# DorothiController.net
KiCad netlist of a schematic drawn in EAGLE
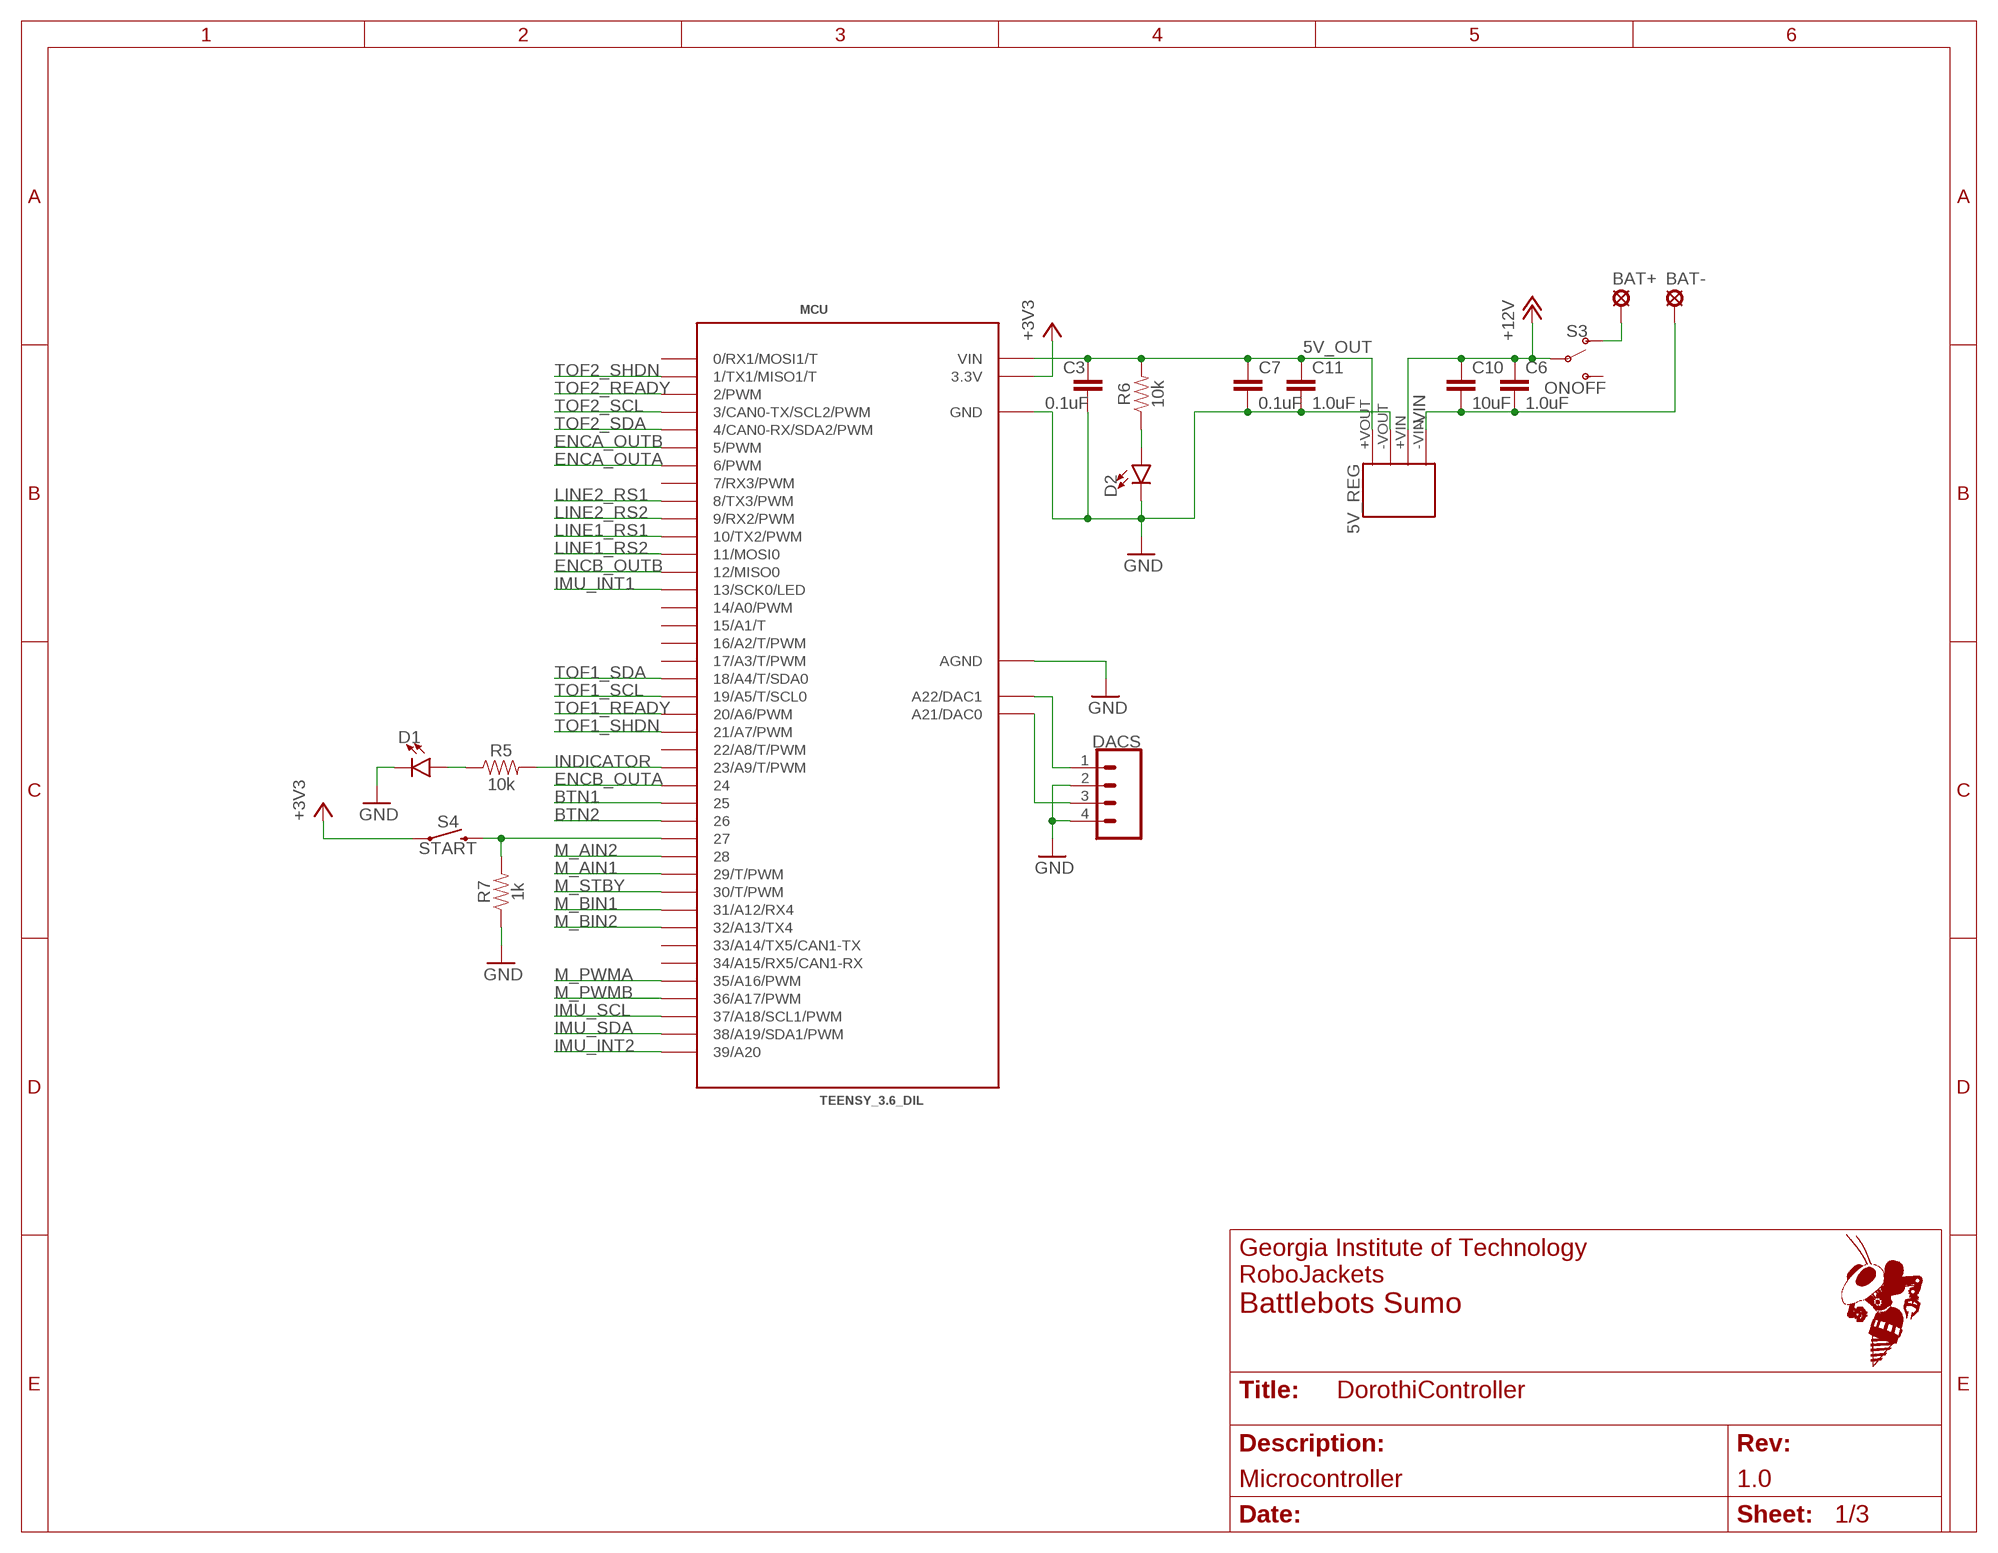
[diagram p0: schematic, sheet 1]
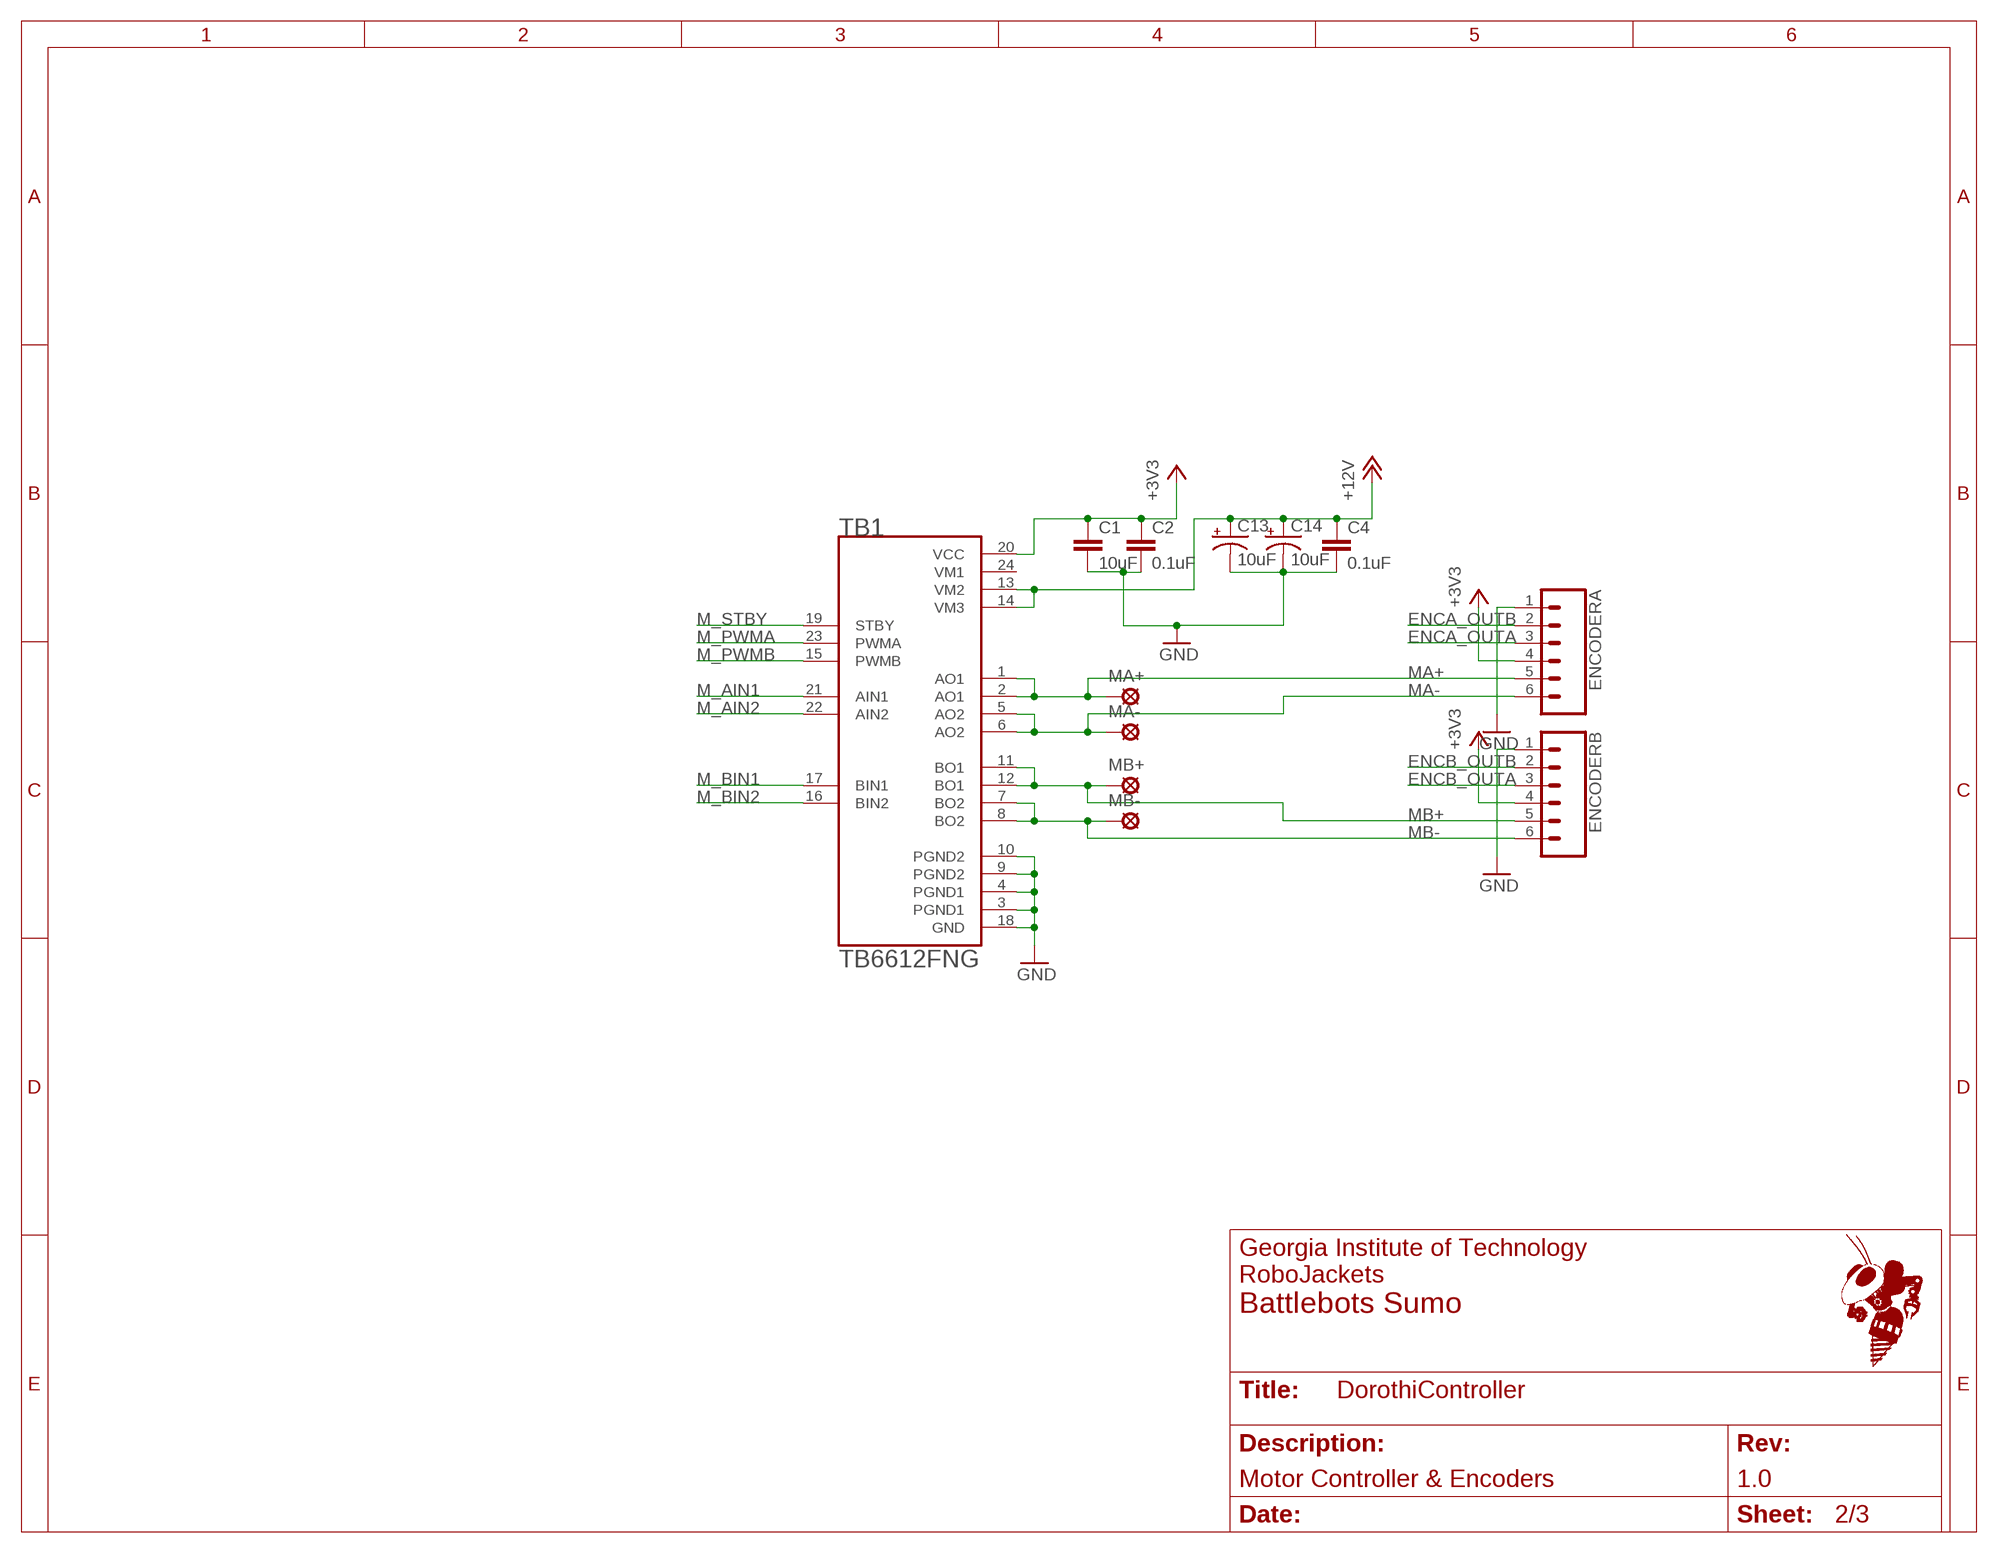
[diagram p1: schematic, sheet 2]
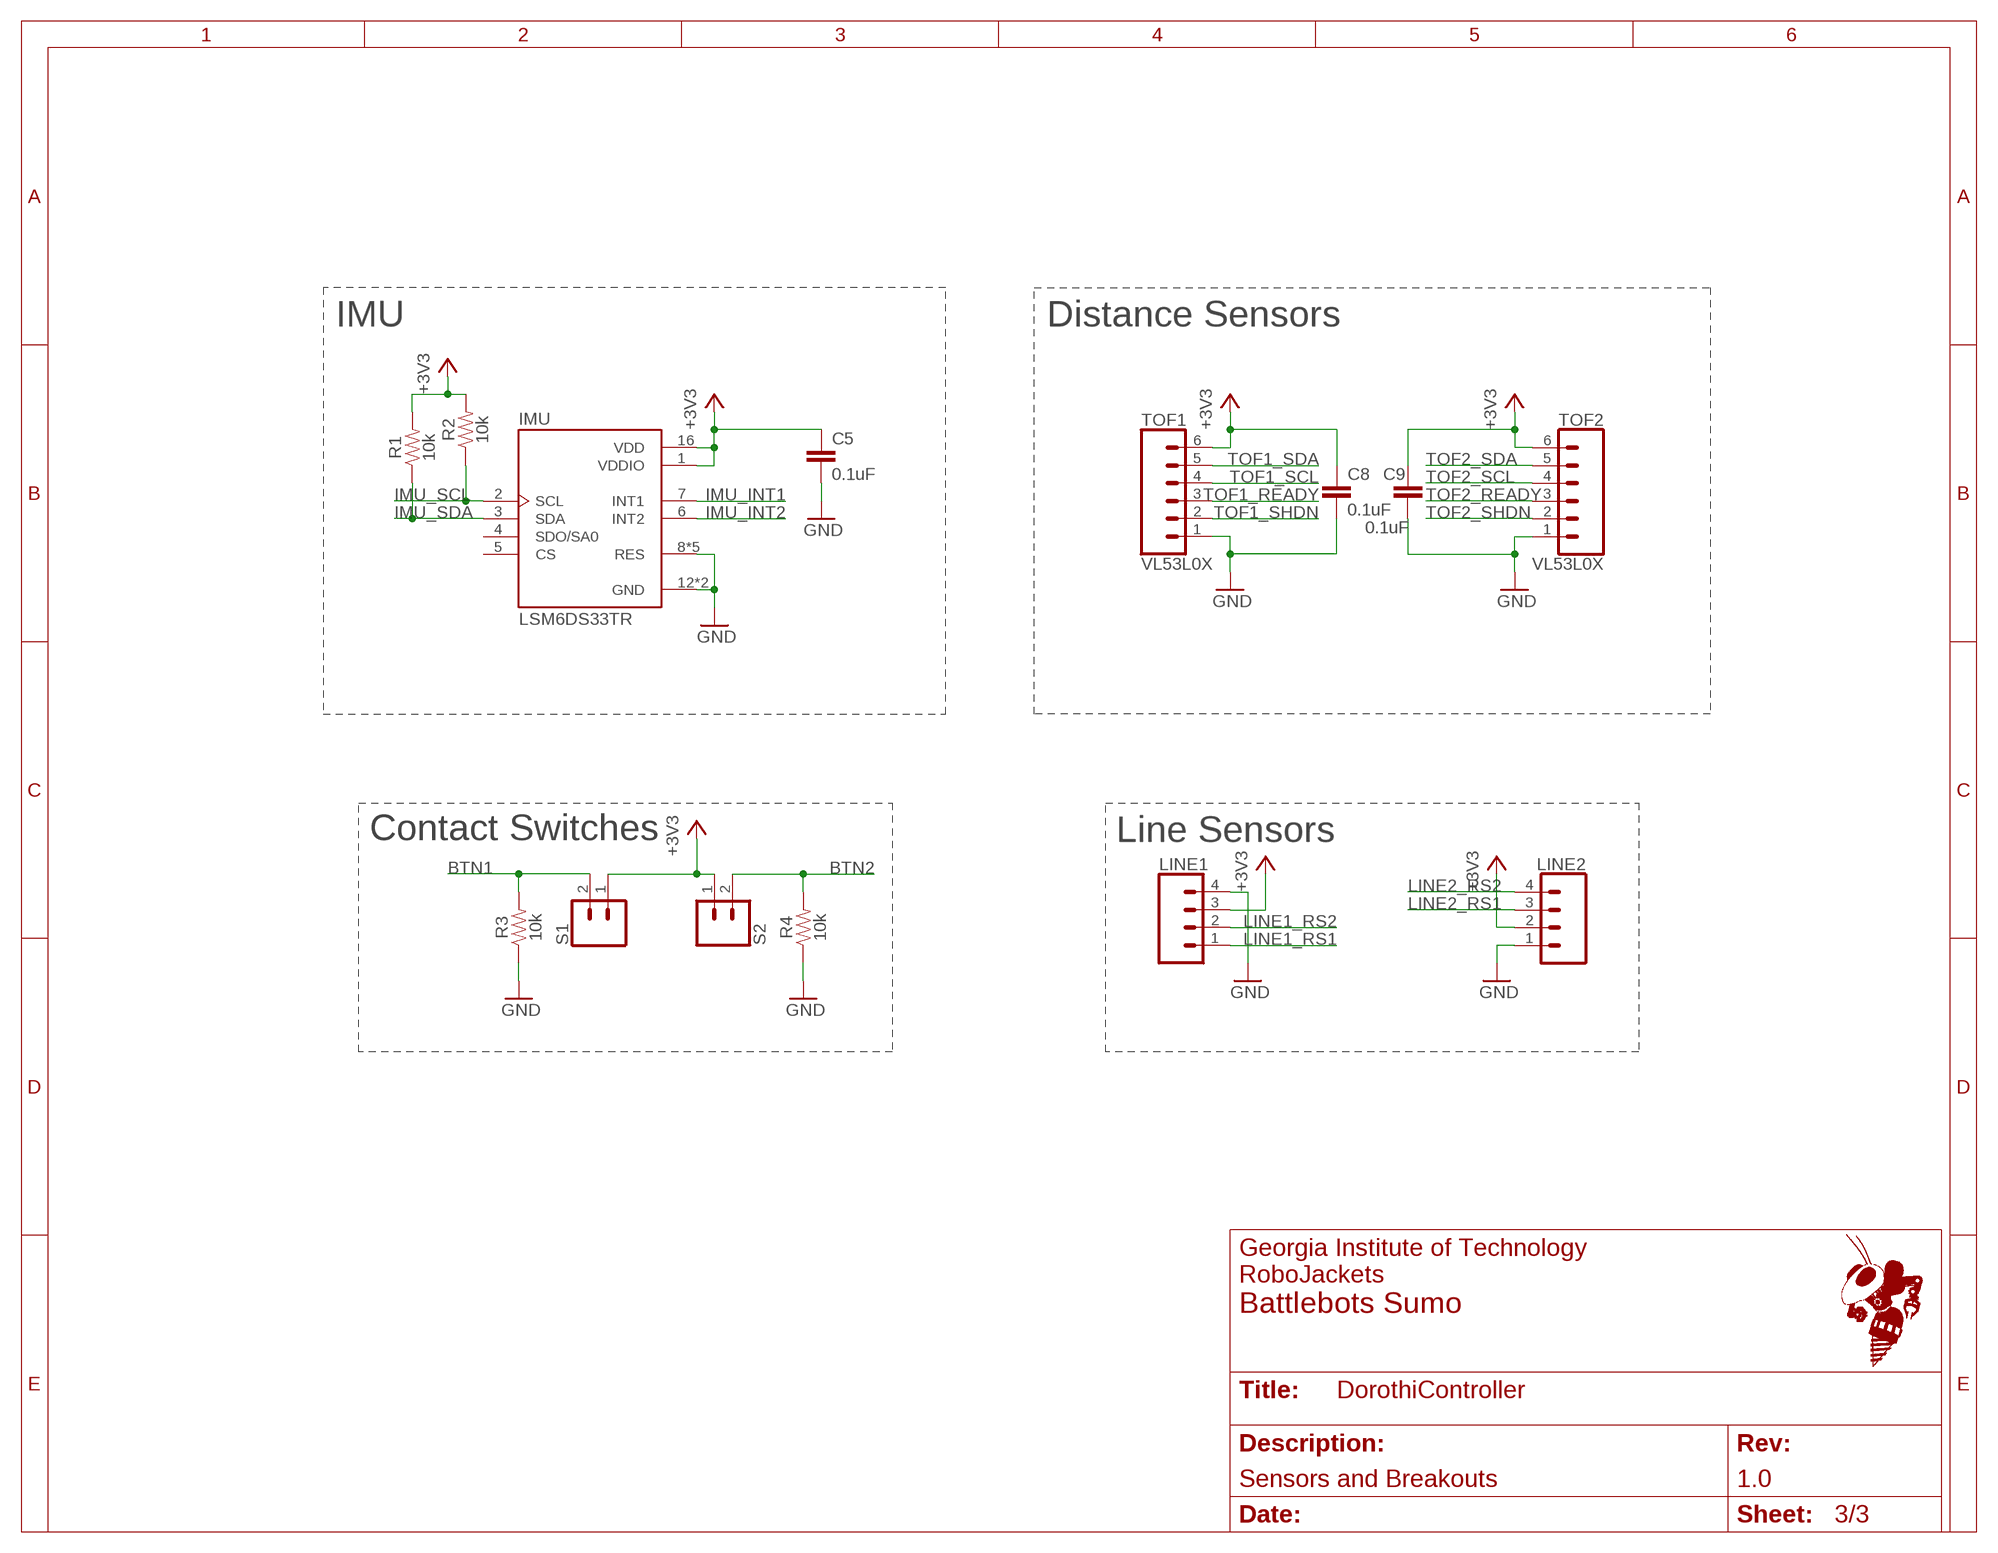
[diagram p2: schematic, sheet 3]

(export (version "E")
  (design (tool "Eeschema 10.0.6"))
  (components
    (comp (ref "C1")
      (value "10uF")
      (footprint "eagle-import:0603")
      (libsource (lib "eagle-import") (part "10UF-0603-6.3V-20%"))
    )
    (comp (ref "C2")
      (value "0.1uF")
      (footprint "eagle-import:0603")
      (libsource (lib "eagle-import") (part "0.1UF-0603-25V-5%"))
    )
    (comp (ref "C4")
      (value "0.1uF")
      (footprint "eagle-import:0603")
      (libsource (lib "eagle-import") (part "0.1UF-0603-25V-5%"))
    )
    (comp (ref "C13")
      (value "10uF")
      (footprint "eagle-import:0603-POLAR")
      (libsource (lib "eagle-import") (part "10UF-POLAR-0603-6.3V-20%(TANT)"))
    )
    (comp (ref "C14")
      (value "10uF")
      (footprint "eagle-import:0603-POLAR")
      (libsource (lib "eagle-import") (part "10UF-POLAR-0603-6.3V-20%(TANT)"))
    )
    (comp (ref "ENCODERA")
      (value "CONN_06SILK_FEMALE_PTH")
      (footprint "eagle-import:1X06")
      (libsource (lib "eagle-import") (part "CONN_06SILK_FEMALE_PTH"))
    )
    (comp (ref "ENCODERB")
      (value "CONN_06SILK_FEMALE_PTH")
      (footprint "eagle-import:1X06")
      (libsource (lib "eagle-import") (part "CONN_06SILK_FEMALE_PTH"))
    )
    (comp (ref "MA+")
      (value "24_SOLPAD")
      (footprint "eagle-import:WIRE_SOLPAD")
      (libsource (lib "eagle-import") (part "24_SOLPAD"))
    )
    (comp (ref "MA-")
      (value "24_SOLPAD")
      (footprint "eagle-import:WIRE_SOLPAD")
      (libsource (lib "eagle-import") (part "24_SOLPAD"))
    )
    (comp (ref "MB+")
      (value "24_SOLPAD")
      (footprint "eagle-import:WIRE_SOLPAD")
      (libsource (lib "eagle-import") (part "24_SOLPAD"))
    )
    (comp (ref "MB-")
      (value "24_SOLPAD")
      (footprint "eagle-import:WIRE_SOLPAD")
      (libsource (lib "eagle-import") (part "24_SOLPAD"))
    )
    (comp (ref "TB1")
      (value "TB6612FNG")
      (footprint "eagle-import:SOP65P760X160-24N")
      (fields (field (name "MF") "Toshiba") (field (name "MP") "TB6612FNG_O,C,8,EL"))
      (libsource (lib "eagle-import") (part "TB6612FNG(O,C,8,EL"))
    )
    (comp (ref "C5")
      (value "0.1uF")
      (footprint "eagle-import:0603")
      (libsource (lib "eagle-import") (part "0.1UF-0603-25V-5%"))
    )
    (comp (ref "C8")
      (value "0.1uF")
      (footprint "eagle-import:0603")
      (libsource (lib "eagle-import") (part "0.1UF-0603-25V-5%"))
    )
    (comp (ref "C9")
      (value "0.1uF")
      (footprint "eagle-import:0603")
      (libsource (lib "eagle-import") (part "0.1UF-0603-25V-5%"))
    )
    (comp (ref "IMU")
      (value "LSM6DS33TR")
      (footprint "eagle-import:PQFN50P300X300X86-16N")
      (fields (field (name "MF") "STMicroelectronics"))
      (libsource (lib "eagle-import") (part "LSM6DS33TR"))
    )
    (comp (ref "LINE1")
      (value "CONN_04")
      (footprint "eagle-import:1X04")
      (libsource (lib "eagle-import") (part "CONN_04"))
    )
    (comp (ref "LINE2")
      (value "CONN_04")
      (footprint "eagle-import:1X04")
      (libsource (lib "eagle-import") (part "CONN_04"))
    )
    (comp (ref "R1")
      (value "10k")
      (footprint "eagle-import:0603")
      (libsource (lib "eagle-import") (part "10KOHM-0603-1/10W-1%"))
    )
    (comp (ref "R2")
      (value "10k")
      (footprint "eagle-import:0603")
      (libsource (lib "eagle-import") (part "10KOHM-0603-1/10W-1%"))
    )
    (comp (ref "R3")
      (value "10k")
      (footprint "eagle-import:0603")
      (libsource (lib "eagle-import") (part "10KOHM-0603-1/10W-1%"))
    )
    (comp (ref "R4")
      (value "10k")
      (footprint "eagle-import:0603")
      (libsource (lib "eagle-import") (part "10KOHM-0603-1/10W-1%"))
    )
    (comp (ref "S1")
      (value "CONN_02")
      (footprint "eagle-import:1X02")
      (libsource (lib "eagle-import") (part "CONN_02"))
    )
    (comp (ref "S2")
      (value "CONN_02")
      (footprint "eagle-import:1X02")
      (libsource (lib "eagle-import") (part "CONN_02"))
    )
    (comp (ref "TOF1")
      (value "VL53L0X")
      (footprint "eagle-import:1X06")
      (libsource (lib "eagle-import") (part "CONN_06SILK_FEMALE_PTH"))
    )
    (comp (ref "TOF2")
      (value "VL53L0X")
      (footprint "eagle-import:1X06")
      (libsource (lib "eagle-import") (part "CONN_06SILK_FEMALE_PTH"))
    )
    (comp (ref "5V_REG")
      (value "CRE1S1205SC")
      (footprint "eagle-import:CRE1S1205SC")
      (libsource (lib "eagle-import") (part "CRE1S1205SC"))
    )
    (comp (ref "BAT+")
      (value "24_SOLPAD")
      (footprint "eagle-import:WIRE_SOLPAD")
      (libsource (lib "eagle-import") (part "24_SOLPAD"))
    )
    (comp (ref "BAT-")
      (value "24_SOLPAD")
      (footprint "eagle-import:WIRE_SOLPAD")
      (libsource (lib "eagle-import") (part "24_SOLPAD"))
    )
    (comp (ref "C3")
      (value "0.1uF")
      (footprint "eagle-import:0603")
      (libsource (lib "eagle-import") (part "SparkFun-Capacitors_510_0.1UF-0603-25V-(+80/-20%)"))
    )
    (comp (ref "C6")
      (value "1.0uF")
      (footprint "eagle-import:0603")
      (libsource (lib "eagle-import") (part "1.0UF-0603-16V-10%"))
    )
    (comp (ref "C7")
      (value "0.1uF")
      (footprint "eagle-import:0603")
      (libsource (lib "eagle-import") (part "SparkFun-Capacitors_510_0.1UF-0603-25V-(+80/-20%)"))
    )
    (comp (ref "C10")
      (value "10uF")
      (footprint "eagle-import:0603")
      (libsource (lib "eagle-import") (part "10UF-0603-6.3V-20%"))
    )
    (comp (ref "C11")
      (value "1.0uF")
      (footprint "eagle-import:0603")
      (libsource (lib "eagle-import") (part "1.0UF-0603-16V-10%"))
    )
    (comp (ref "D1")
      (value "LED0603")
      (footprint "eagle-import:LED-0603")
      (libsource (lib "eagle-import") (part "LED0603"))
    )
    (comp (ref "D2")
      (value "LED0603")
      (footprint "eagle-import:LED-0603")
      (libsource (lib "eagle-import") (part "LED0603"))
    )
    (comp (ref "DACS")
      (value "CONN_04")
      (footprint "eagle-import:1X04")
      (libsource (lib "eagle-import") (part "CONN_04"))
    )
    (comp (ref "MCU")
      (value "TEENSY_3.6_DIL")
      (footprint "eagle-import:TEENSY_3.6_DIL")
      (libsource (lib "eagle-import") (part "TEENSY_3.6_DIL"))
    )
    (comp (ref "R5")
      (value "10k")
      (footprint "eagle-import:0603")
      (libsource (lib "eagle-import") (part "10KOHM-0603-1/10W-1%"))
    )
    (comp (ref "R6")
      (value "10k")
      (footprint "eagle-import:0603")
      (libsource (lib "eagle-import") (part "10KOHM-0603-1/10W-1%"))
    )
    (comp (ref "R7")
      (value "1k")
      (footprint "eagle-import:0603")
      (libsource (lib "eagle-import") (part "1KOHM-0603-1/10W-1%"))
    )
    (comp (ref "S3")
      (value "ONOFF")
      (footprint "eagle-import:SWITCH_SPDT_PTH_11.6X4.0MM")
      (libsource (lib "eagle-import") (part "SWITCH-SPDT-PTH-11.6X4.0MM"))
    )
    (comp (ref "S4")
      (value "START")
      (footprint "eagle-import:TACTILE_SWITCH_SMD_6.0X3.5MM")
      (libsource (lib "eagle-import") (part "MOMENTARY-SWITCH-SPST-SMD-6.0X3.5MM"))
    )
  )
  (nets
    (net (code "1") (name "+3V3") (class "Default")
      (node (ref "C1") (pin "1") (pinfunction "1_1") (pintype "passive"))
      (node (ref "C2") (pin "1") (pinfunction "1_1") (pintype "passive"))
      (node (ref "C5") (pin "1") (pinfunction "1_1") (pintype "passive"))
      (node (ref "C8") (pin "1") (pinfunction "1_1") (pintype "passive"))
      (node (ref "C9") (pin "1") (pinfunction "1_1") (pintype "passive"))
      (node (ref "ENCODERA") (pin "4") (pinfunction "4_4") (pintype "passive"))
      (node (ref "ENCODERB") (pin "4") (pinfunction "4_4") (pintype "passive"))
      (node (ref "IMU") (pin "1") (pinfunction "VDDIO_1") (pintype "power_in"))
      (node (ref "IMU") (pin "16") (pinfunction "VDD_16") (pintype "power_in"))
      (node (ref "LINE1") (pin "3") (pinfunction "3_3") (pintype "passive"))
      (node (ref "LINE2") (pin "2") (pinfunction "2_2") (pintype "passive"))
      (node (ref "MCU") (pin "3.3V") (pinfunction "3.3V_3.3V") (pintype "power_in"))
      (node (ref "MCU") (pin "3.3V3") (pinfunction "3.3V_3.3V3") (pintype "power_in"))
      (node (ref "R1") (pin "2") (pinfunction "2_2") (pintype "passive"))
      (node (ref "R2") (pin "2") (pinfunction "2_2") (pintype "passive"))
      (node (ref "S1") (pin "1") (pinfunction "1_1") (pintype "passive"))
      (node (ref "S2") (pin "1") (pinfunction "1_1") (pintype "passive"))
      (node (ref "S4") (pin "1") (pinfunction "1_1") (pintype "passive"))
      (node (ref "TB1") (pin "20") (pinfunction "VCC_20") (pintype "power_in"))
      (node (ref "TOF1") (pin "6") (pinfunction "6_6") (pintype "passive"))
      (node (ref "TOF2") (pin "6") (pinfunction "6_6") (pintype "passive"))
    )
    (net (code "2") (name "+12V") (class "Default")
      (node (ref "5V_REG") (pin "+VIN") (pinfunction "+VIN_+VIN") (pintype "bidirectional"))
      (node (ref "C10") (pin "1") (pinfunction "1_1") (pintype "passive"))
      (node (ref "C13") (pin "+") (pinfunction "+_+") (pintype "passive"))
      (node (ref "C14") (pin "+") (pinfunction "+_+") (pintype "passive"))
      (node (ref "C4") (pin "1") (pinfunction "1_1") (pintype "passive"))
      (node (ref "C6") (pin "1") (pinfunction "1_1") (pintype "passive"))
      (node (ref "S3") (pin "2") (pinfunction "P_2") (pintype "passive"))
      (node (ref "TB1") (pin "13") (pinfunction "VM2_13") (pintype "power_in"))
      (node (ref "TB1") (pin "14") (pinfunction "VM3_14") (pintype "power_in"))
    )
    (net (code "3") (name "-VIN") (class "Default")
      (node (ref "5V_REG") (pin "-VIN") (pinfunction "-VIN_-VIN") (pintype "bidirectional"))
      (node (ref "BAT-") (pin "P$1") (pinfunction "MP_P$1") (pintype "passive"))
      (node (ref "C10") (pin "2") (pinfunction "2_2") (pintype "passive"))
      (node (ref "C6") (pin "2") (pinfunction "2_2") (pintype "passive"))
    )
    (net (code "4") (name "5V_OUT") (class "Default")
      (node (ref "5V_REG") (pin "+VOUT") (pinfunction "+VOUT_+VOUT") (pintype "bidirectional"))
      (node (ref "C11") (pin "1") (pinfunction "1_1") (pintype "passive"))
      (node (ref "C3") (pin "1") (pinfunction "1_1") (pintype "passive"))
      (node (ref "C7") (pin "1") (pinfunction "1_1") (pintype "passive"))
      (node (ref "MCU") (pin "VIN") (pinfunction "VIN_VIN") (pintype "power_in"))
      (node (ref "R6") (pin "2") (pinfunction "2_2") (pintype "passive"))
    )
    (net (code "5") (name "BTN1") (class "Default")
      (node (ref "MCU") (pin "25") (pinfunction "25_25") (pintype "bidirectional"))
      (node (ref "R3") (pin "2") (pinfunction "2_2") (pintype "passive"))
      (node (ref "S1") (pin "2") (pinfunction "2_2") (pintype "passive"))
    )
    (net (code "6") (name "BTN2") (class "Default")
      (node (ref "MCU") (pin "26") (pinfunction "26_26") (pintype "bidirectional"))
      (node (ref "R4") (pin "2") (pinfunction "2_2") (pintype "passive"))
      (node (ref "S2") (pin "2") (pinfunction "2_2") (pintype "passive"))
    )
    (net (code "7") (name "ENCA_OUTA") (class "Default")
      (node (ref "ENCODERA") (pin "3") (pinfunction "3_3") (pintype "passive"))
      (node (ref "MCU") (pin "6") (pinfunction "6/PWM_6") (pintype "bidirectional"))
    )
    (net (code "8") (name "ENCA_OUTB") (class "Default")
      (node (ref "ENCODERA") (pin "2") (pinfunction "2_2") (pintype "passive"))
      (node (ref "MCU") (pin "5") (pinfunction "5/PWM_5") (pintype "bidirectional"))
    )
    (net (code "9") (name "ENCB_OUTA") (class "Default")
      (node (ref "ENCODERB") (pin "3") (pinfunction "3_3") (pintype "passive"))
      (node (ref "MCU") (pin "24") (pinfunction "24_24") (pintype "bidirectional"))
    )
    (net (code "10") (name "ENCB_OUTB") (class "Default")
      (node (ref "ENCODERB") (pin "2") (pinfunction "2_2") (pintype "passive"))
      (node (ref "MCU") (pin "12") (pinfunction "12/MISO0_12") (pintype "bidirectional"))
    )
    (net (code "11") (name "GND") (class "Default")
      (node (ref "5V_REG") (pin "-VOUT") (pinfunction "-VOUT_-VOUT") (pintype "bidirectional"))
      (node (ref "C1") (pin "2") (pinfunction "2_2") (pintype "passive"))
      (node (ref "C11") (pin "2") (pinfunction "2_2") (pintype "passive"))
      (node (ref "C13") (pin "-") (pinfunction "-_-") (pintype "passive"))
      (node (ref "C14") (pin "-") (pinfunction "-_-") (pintype "passive"))
      (node (ref "C2") (pin "2") (pinfunction "2_2") (pintype "passive"))
      (node (ref "C3") (pin "2") (pinfunction "2_2") (pintype "passive"))
      (node (ref "C4") (pin "2") (pinfunction "2_2") (pintype "passive"))
      (node (ref "C5") (pin "2") (pinfunction "2_2") (pintype "passive"))
      (node (ref "C7") (pin "2") (pinfunction "2_2") (pintype "passive"))
      (node (ref "C8") (pin "2") (pinfunction "2_2") (pintype "passive"))
      (node (ref "C9") (pin "2") (pinfunction "2_2") (pintype "passive"))
      (node (ref "D1") (pin "C") (pinfunction "C_C") (pintype "passive"))
      (node (ref "D2") (pin "C") (pinfunction "C_C") (pintype "passive"))
      (node (ref "DACS") (pin "2") (pinfunction "2_2") (pintype "passive"))
      (node (ref "DACS") (pin "4") (pinfunction "4_4") (pintype "passive"))
      (node (ref "ENCODERA") (pin "1") (pinfunction "1_1") (pintype "passive"))
      (node (ref "ENCODERB") (pin "1") (pinfunction "1_1") (pintype "passive"))
      (node (ref "IMU") (pin "10") (pinfunction "RES_10") (pintype "passive"))
      (node (ref "IMU") (pin "11") (pinfunction "RES_11") (pintype "passive"))
      (node (ref "IMU") (pin "12") (pinfunction "GND_12") (pintype "power_in"))
      (node (ref "IMU") (pin "13") (pinfunction "GND_13") (pintype "power_in"))
      (node (ref "IMU") (pin "15") (pinfunction "RES_15") (pintype "passive"))
      (node (ref "IMU") (pin "8") (pinfunction "RES_8") (pintype "passive"))
      (node (ref "IMU") (pin "9") (pinfunction "RES_9") (pintype "passive"))
      (node (ref "LINE1") (pin "4") (pinfunction "4_4") (pintype "passive"))
      (node (ref "LINE2") (pin "1") (pinfunction "1_1") (pintype "passive"))
      (node (ref "MCU") (pin "AGND") (pinfunction "AGND_AGND") (pintype "power_in"))
      (node (ref "MCU") (pin "GND") (pinfunction "GND_GND") (pintype "power_in"))
      (node (ref "MCU") (pin "GND1") (pinfunction "GND_GND1") (pintype "power_in"))
      (node (ref "R3") (pin "1") (pinfunction "1_1") (pintype "passive"))
      (node (ref "R4") (pin "1") (pinfunction "1_1") (pintype "passive"))
      (node (ref "R7") (pin "1") (pinfunction "1_1") (pintype "passive"))
      (node (ref "TB1") (pin "10") (pinfunction "PGND2_10") (pintype "passive"))
      (node (ref "TB1") (pin "18") (pinfunction "GND_18") (pintype "passive"))
      (node (ref "TB1") (pin "3") (pinfunction "PGND1_3") (pintype "passive"))
      (node (ref "TB1") (pin "4") (pinfunction "PGND1_4") (pintype "passive"))
      (node (ref "TB1") (pin "9") (pinfunction "PGND2_9") (pintype "passive"))
      (node (ref "TOF1") (pin "1") (pinfunction "1_1") (pintype "passive"))
      (node (ref "TOF2") (pin "1") (pinfunction "1_1") (pintype "passive"))
    )
    (net (code "12") (name "IMU_INT1") (class "Default")
      (node (ref "IMU") (pin "7") (pinfunction "INT1_7") (pintype "output"))
      (node (ref "MCU") (pin "13") (pinfunction "13/SCK0/LED_13") (pintype "bidirectional"))
    )
    (net (code "13") (name "IMU_INT2") (class "Default")
      (node (ref "IMU") (pin "6") (pinfunction "INT2_6") (pintype "output"))
      (node (ref "MCU") (pin "39/A20") (pinfunction "39/A20_39/A20") (pintype "bidirectional"))
    )
    (net (code "14") (name "IMU_SCL") (class "Default")
      (node (ref "IMU") (pin "2") (pinfunction "SCL_2") (pintype "bidirectional"))
      (node (ref "MCU") (pin "37/A18") (pinfunction "37/A18/SCL1/PWM_37/A18") (pintype "bidirectional"))
      (node (ref "R2") (pin "1") (pinfunction "1_1") (pintype "passive"))
    )
    (net (code "15") (name "IMU_SDA") (class "Default")
      (node (ref "IMU") (pin "3") (pinfunction "SDA_3") (pintype "bidirectional"))
      (node (ref "MCU") (pin "38/A19") (pinfunction "38/A19/SDA1/PWM_38/A19") (pintype "bidirectional"))
      (node (ref "R1") (pin "1") (pinfunction "1_1") (pintype "passive"))
    )
    (net (code "16") (name "INDICATOR") (class "Default")
      (node (ref "MCU") (pin "23/A9") (pinfunction "23/A9/T/PWM_23/A9") (pintype "bidirectional"))
      (node (ref "R5") (pin "2") (pinfunction "2_2") (pintype "passive"))
    )
    (net (code "17") (name "LINE1_RS1") (class "Default")
      (node (ref "LINE1") (pin "1") (pinfunction "1_1") (pintype "passive"))
      (node (ref "MCU") (pin "10") (pinfunction "10/TX2/PWM_10") (pintype "bidirectional"))
    )
    (net (code "18") (name "LINE1_RS2") (class "Default")
      (node (ref "LINE1") (pin "2") (pinfunction "2_2") (pintype "passive"))
      (node (ref "MCU") (pin "11") (pinfunction "11/MOSI0_11") (pintype "bidirectional"))
    )
    (net (code "19") (name "LINE2_RS1") (class "Default")
      (node (ref "LINE2") (pin "3") (pinfunction "3_3") (pintype "passive"))
      (node (ref "MCU") (pin "8") (pinfunction "8/TX3/PWM_8") (pintype "bidirectional"))
    )
    (net (code "20") (name "LINE2_RS2") (class "Default")
      (node (ref "LINE2") (pin "4") (pinfunction "4_4") (pintype "passive"))
      (node (ref "MCU") (pin "9") (pinfunction "9/RX2/PWM_9") (pintype "bidirectional"))
    )
    (net (code "21") (name "MA+") (class "Default")
      (node (ref "ENCODERA") (pin "5") (pinfunction "5_5") (pintype "passive"))
      (node (ref "MA+") (pin "P$1") (pinfunction "MP_P$1") (pintype "passive"))
      (node (ref "TB1") (pin "1") (pinfunction "AO1_1") (pintype "bidirectional"))
      (node (ref "TB1") (pin "2") (pinfunction "AO1_2") (pintype "bidirectional"))
    )
    (net (code "22") (name "MA-") (class "Default")
      (node (ref "ENCODERA") (pin "6") (pinfunction "6_6") (pintype "passive"))
      (node (ref "MA-") (pin "P$1") (pinfunction "MP_P$1") (pintype "passive"))
      (node (ref "TB1") (pin "5") (pinfunction "AO2_5") (pintype "bidirectional"))
      (node (ref "TB1") (pin "6") (pinfunction "AO2_6") (pintype "bidirectional"))
    )
    (net (code "23") (name "MB+") (class "Default")
      (node (ref "ENCODERB") (pin "5") (pinfunction "5_5") (pintype "passive"))
      (node (ref "MB+") (pin "P$1") (pinfunction "MP_P$1") (pintype "passive"))
      (node (ref "TB1") (pin "11") (pinfunction "BO1_11") (pintype "bidirectional"))
      (node (ref "TB1") (pin "12") (pinfunction "BO1_12") (pintype "bidirectional"))
    )
    (net (code "24") (name "MB-") (class "Default")
      (node (ref "ENCODERB") (pin "6") (pinfunction "6_6") (pintype "passive"))
      (node (ref "MB-") (pin "P$1") (pinfunction "MP_P$1") (pintype "passive"))
      (node (ref "TB1") (pin "7") (pinfunction "BO2_7") (pintype "bidirectional"))
      (node (ref "TB1") (pin "8") (pinfunction "BO2_8") (pintype "bidirectional"))
    )
    (net (code "25") (name "M_AIN1") (class "Default")
      (node (ref "MCU") (pin "29") (pinfunction "29/T/PWM_29") (pintype "bidirectional"))
      (node (ref "TB1") (pin "21") (pinfunction "AIN1_21") (pintype "input"))
    )
    (net (code "26") (name "M_AIN2") (class "Default")
      (node (ref "MCU") (pin "28") (pinfunction "28_28") (pintype "bidirectional"))
      (node (ref "TB1") (pin "22") (pinfunction "AIN2_22") (pintype "input"))
    )
    (net (code "27") (name "M_BIN1") (class "Default")
      (node (ref "MCU") (pin "31/A12") (pinfunction "31/A12/RX4_31/A12") (pintype "bidirectional"))
      (node (ref "TB1") (pin "17") (pinfunction "BIN1_17") (pintype "input"))
    )
    (net (code "28") (name "M_BIN2") (class "Default")
      (node (ref "MCU") (pin "32/A13") (pinfunction "32/A13/TX4_32/A13") (pintype "bidirectional"))
      (node (ref "TB1") (pin "16") (pinfunction "BIN2_16") (pintype "input"))
    )
    (net (code "29") (name "M_PWMA") (class "Default")
      (node (ref "MCU") (pin "35/A16") (pinfunction "35/A16/PWM_35/A16") (pintype "bidirectional"))
      (node (ref "TB1") (pin "23") (pinfunction "PWMA_23") (pintype "input"))
    )
    (net (code "30") (name "M_PWMB") (class "Default")
      (node (ref "MCU") (pin "36/A17") (pinfunction "36/A17/PWM_36/A17") (pintype "bidirectional"))
      (node (ref "TB1") (pin "15") (pinfunction "PWMB_15") (pintype "input"))
    )
    (net (code "31") (name "M_STBY") (class "Default")
      (node (ref "MCU") (pin "30") (pinfunction "30/T/PWM_30") (pintype "bidirectional"))
      (node (ref "TB1") (pin "19") (pinfunction "STBY_19") (pintype "input"))
    )
    (net (code "32") (name "Net-(BAT+-MP)") (class "Default")
      (node (ref "BAT+") (pin "P$1") (pinfunction "MP_P$1") (pintype "passive"))
      (node (ref "S3") (pin "1") (pinfunction "O_1") (pintype "passive"))
    )
    (net (code "33") (name "Net-(D1-PadA)") (class "Default")
      (node (ref "D1") (pin "A") (pinfunction "A_A") (pintype "passive"))
      (node (ref "R5") (pin "1") (pinfunction "1_1") (pintype "passive"))
    )
    (net (code "34") (name "Net-(D2-PadA)") (class "Default")
      (node (ref "D2") (pin "A") (pinfunction "A_A") (pintype "passive"))
      (node (ref "R6") (pin "1") (pinfunction "1_1") (pintype "passive"))
    )
    (net (code "35") (name "Net-(MCU-A21{slash}DAC0)") (class "Default")
      (node (ref "DACS") (pin "3") (pinfunction "3_3") (pintype "passive"))
      (node (ref "MCU") (pin "A21") (pinfunction "A21/DAC0_A21") (pintype "bidirectional"))
    )
    (net (code "36") (name "Net-(MCU-A22{slash}DAC1)") (class "Default")
      (node (ref "DACS") (pin "1") (pinfunction "1_1") (pintype "passive"))
      (node (ref "MCU") (pin "A22") (pinfunction "A22/DAC1_A22") (pintype "bidirectional"))
    )
    (net (code "37") (name "Net-(MCU-Pad27)") (class "Default")
      (node (ref "MCU") (pin "27") (pinfunction "27_27") (pintype "bidirectional"))
      (node (ref "R7") (pin "2") (pinfunction "2_2") (pintype "passive"))
      (node (ref "S4") (pin "2") (pinfunction "2_2") (pintype "passive"))
    )
    (net (code "38") (name "TOF1_READY") (class "Default")
      (node (ref "MCU") (pin "20/A6") (pinfunction "20/A6/PWM_20/A6") (pintype "bidirectional"))
      (node (ref "TOF1") (pin "3") (pinfunction "3_3") (pintype "passive"))
    )
    (net (code "39") (name "TOF1_SCL") (class "Default")
      (node (ref "MCU") (pin "19/A5") (pinfunction "19/A5/T/SCL0_19/A5") (pintype "bidirectional"))
      (node (ref "TOF1") (pin "4") (pinfunction "4_4") (pintype "passive"))
    )
    (net (code "40") (name "TOF1_SDA") (class "Default")
      (node (ref "MCU") (pin "18/A4") (pinfunction "18/A4/T/SDA0_18/A4") (pintype "bidirectional"))
      (node (ref "TOF1") (pin "5") (pinfunction "5_5") (pintype "passive"))
    )
    (net (code "41") (name "TOF1_SHDN") (class "Default")
      (node (ref "MCU") (pin "21/A7") (pinfunction "21/A7/PWM_21/A7") (pintype "bidirectional"))
      (node (ref "TOF1") (pin "2") (pinfunction "2_2") (pintype "passive"))
    )
    (net (code "42") (name "TOF2_READY") (class "Default")
      (node (ref "MCU") (pin "2") (pinfunction "2/PWM_2") (pintype "bidirectional"))
      (node (ref "TOF2") (pin "3") (pinfunction "3_3") (pintype "passive"))
    )
    (net (code "43") (name "TOF2_SCL") (class "Default")
      (node (ref "MCU") (pin "3") (pinfunction "3/CAN0-TX/SCL2/PWM_3") (pintype "bidirectional"))
      (node (ref "TOF2") (pin "4") (pinfunction "4_4") (pintype "passive"))
    )
    (net (code "44") (name "TOF2_SDA") (class "Default")
      (node (ref "MCU") (pin "4") (pinfunction "4/CAN0-RX/SDA2/PWM_4") (pintype "bidirectional"))
      (node (ref "TOF2") (pin "5") (pinfunction "5_5") (pintype "passive"))
    )
    (net (code "45") (name "TOF2_SHDN") (class "Default")
      (node (ref "MCU") (pin "1") (pinfunction "1/TX1/MISO1/T_1") (pintype "bidirectional"))
      (node (ref "TOF2") (pin "2") (pinfunction "2_2") (pintype "passive"))
    )
    (net (code "46") (name "VM1") (class "Default")
      (node (ref "TB1") (pin "24") (pinfunction "VM1_24") (pintype "power_in"))
    )
    (net (code "47") (name "unconnected-(IMU-CS-Pad5)") (class "Default")
      (node (ref "IMU") (pin "5") (pinfunction "CS_5") (pintype "bidirectional"))
    )
    (net (code "48") (name "unconnected-(IMU-SDO{slash}SA0-Pad4)") (class "Default")
      (node (ref "IMU") (pin "4") (pinfunction "SDO/SA0_4") (pintype "bidirectional"))
    )
    (net (code "49") (name "unconnected-(MCU-0{slash}RX1{slash}MOSI1{slash}T-Pad0)") (class "Default")
      (node (ref "MCU") (pin "0") (pinfunction "0/RX1/MOSI1/T_0") (pintype "bidirectional"))
    )
    (net (code "50") (name "unconnected-(MCU-7{slash}RX3{slash}PWM-Pad7)") (class "Default")
      (node (ref "MCU") (pin "7") (pinfunction "7/RX3/PWM_7") (pintype "bidirectional"))
    )
    (net (code "51") (name "unconnected-(MCU-14{slash}A0{slash}PWM-Pad14{slash}A0)") (class "Default")
      (node (ref "MCU") (pin "14/A0") (pinfunction "14/A0/PWM_14/A0") (pintype "bidirectional"))
    )
    (net (code "52") (name "unconnected-(MCU-15{slash}A1{slash}T-Pad15{slash}A1)") (class "Default")
      (node (ref "MCU") (pin "15/A1") (pinfunction "15/A1/T_15/A1") (pintype "bidirectional"))
    )
    (net (code "53") (name "unconnected-(MCU-16{slash}A2{slash}T{slash}PWM-Pad16{slash}A2)") (class "Default")
      (node (ref "MCU") (pin "16/A2") (pinfunction "16/A2/T/PWM_16/A2") (pintype "bidirectional"))
    )
    (net (code "54") (name "unconnected-(MCU-17{slash}A3{slash}T{slash}PWM-Pad17{slash}A3)") (class "Default")
      (node (ref "MCU") (pin "17/A3") (pinfunction "17/A3/T/PWM_17/A3") (pintype "bidirectional"))
    )
    (net (code "55") (name "unconnected-(MCU-22{slash}A8{slash}T{slash}PWM-Pad22{slash}A8)") (class "Default")
      (node (ref "MCU") (pin "22/A8") (pinfunction "22/A8/T/PWM_22/A8") (pintype "bidirectional"))
    )
    (net (code "56") (name "unconnected-(MCU-33{slash}A14{slash}TX5{slash}CAN1-TX-Pad33{slash}A14)") (class "Default")
      (node (ref "MCU") (pin "33/A14") (pinfunction "33/A14/TX5/CAN1-TX_33/A14") (pintype "bidirectional"))
    )
    (net (code "57") (name "unconnected-(MCU-34{slash}A15{slash}RX5{slash}CAN1-RX-Pad34{slash}A15)") (class "Default")
      (node (ref "MCU") (pin "34/A15") (pinfunction "34/A15/RX5/CAN1-RX_34/A15") (pintype "bidirectional"))
    )
    (net (code "58") (name "unconnected-(S3-S-Pad3)") (class "Default")
      (node (ref "S3") (pin "3") (pinfunction "S_3") (pintype "passive"))
    )
  )
)
